# gd.net
KiCad netlist of a schematic drawn in Altium Designer
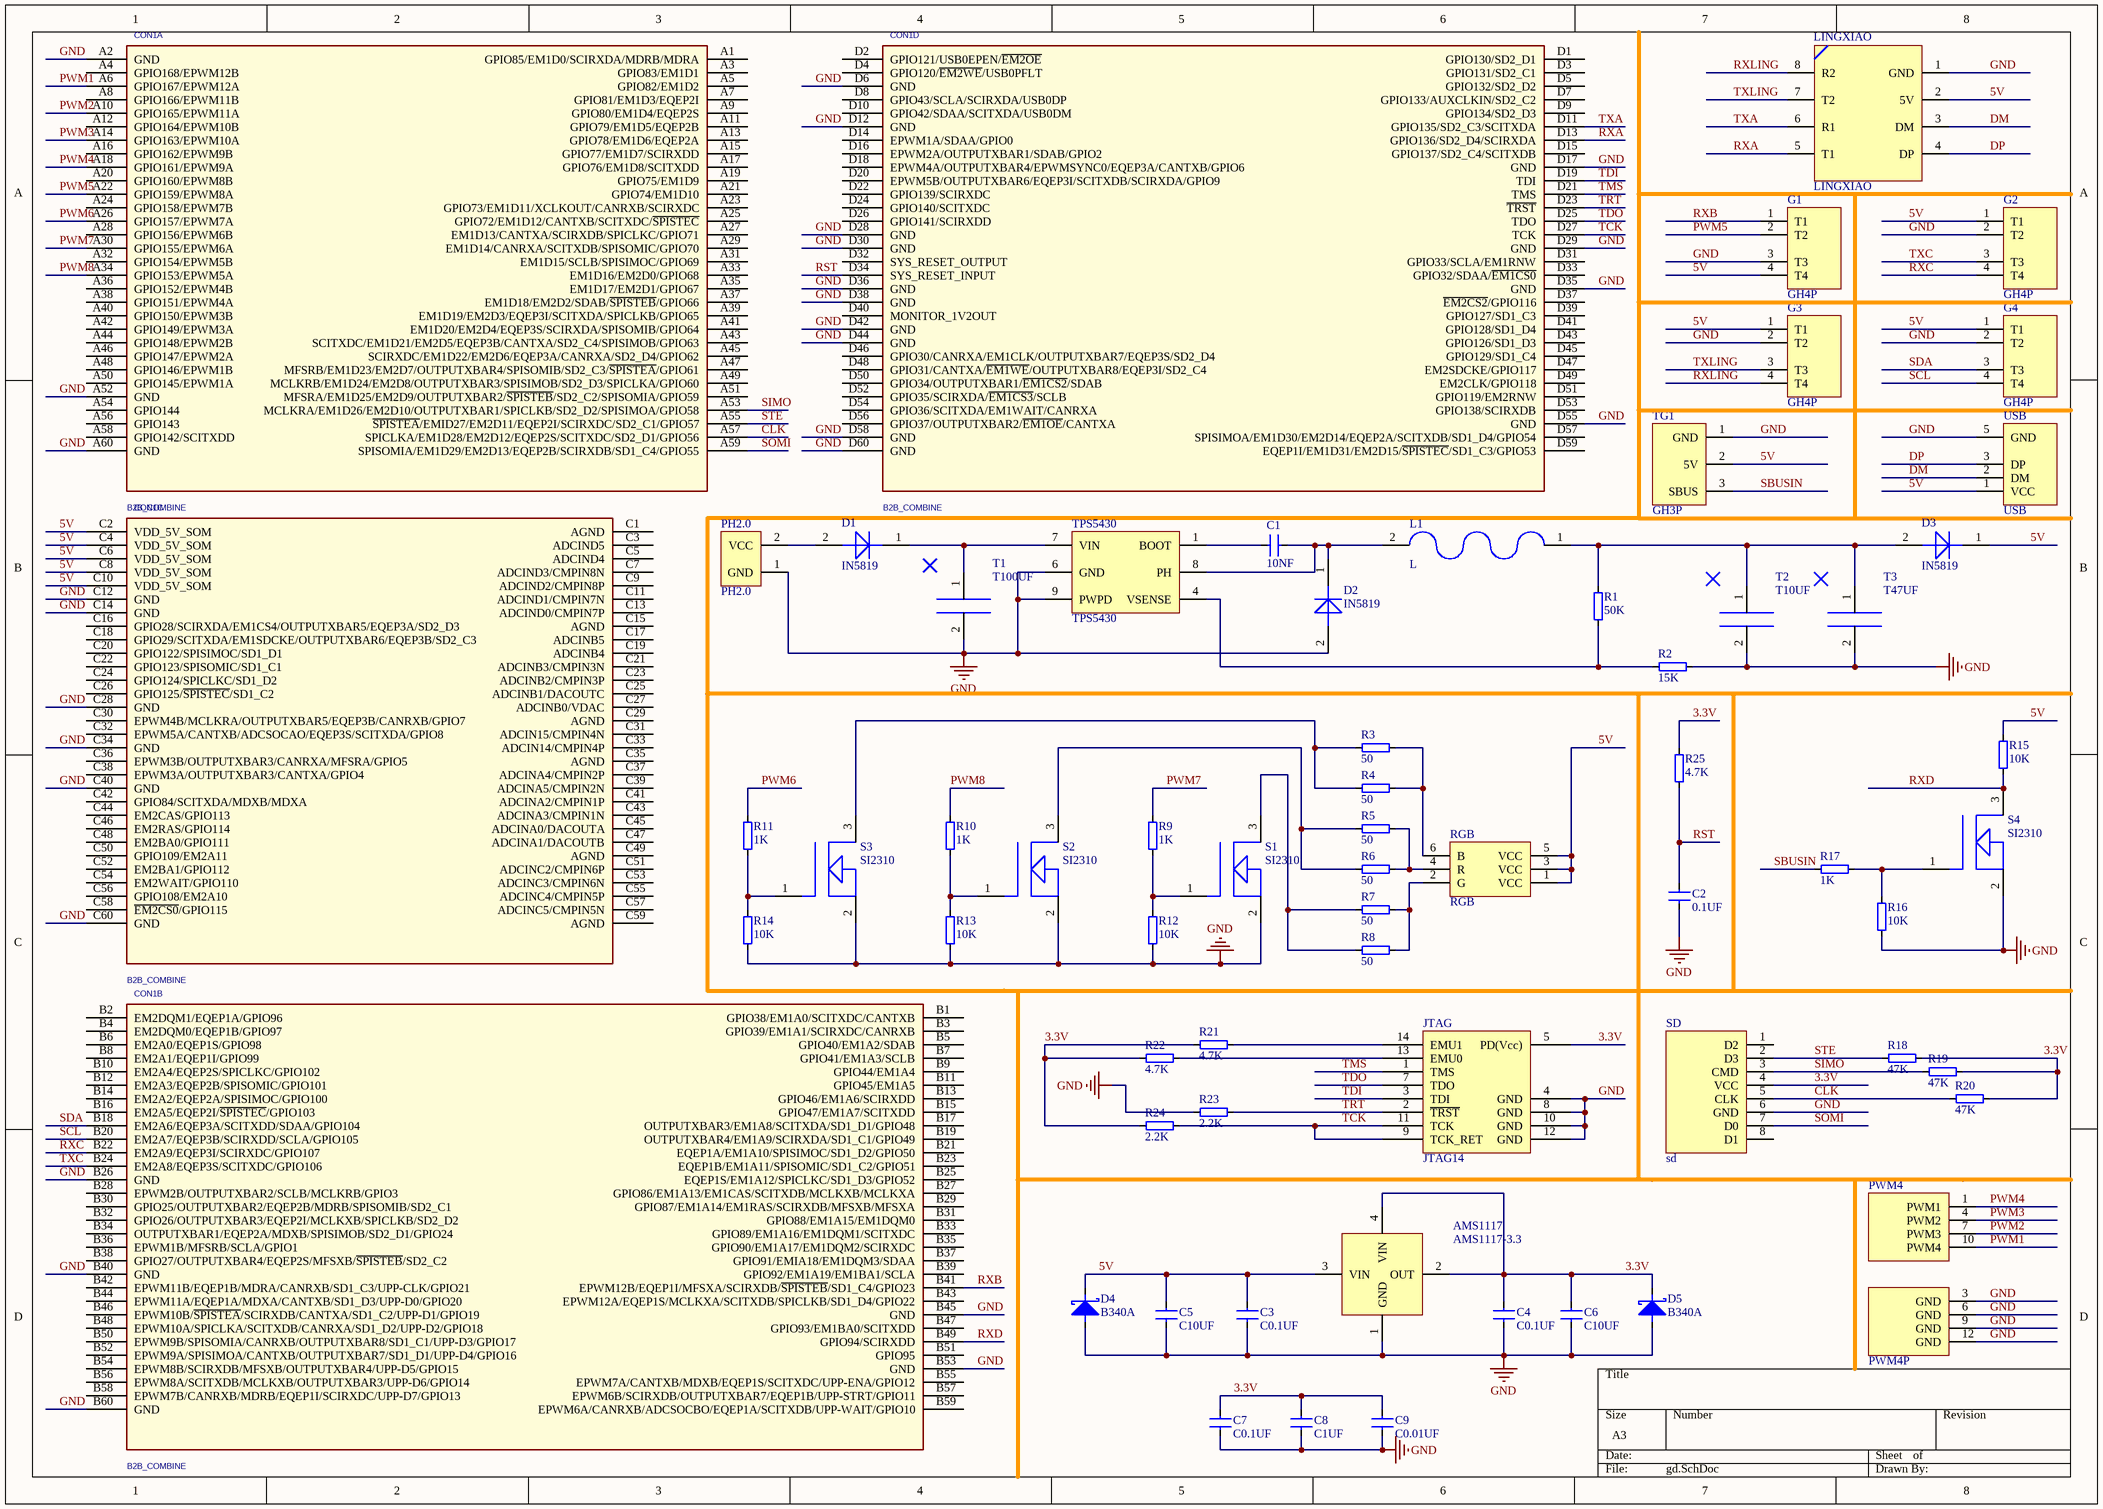
[diagram p0: gd.SchDoc]

(export (version "E")
  (design (tool "Eeschema 10.0.6"))
  (components
    (comp (ref "AMS1117")
      (value "AMS1117-3.3")
      (footprint "SOT-223")
      (libsource (lib "TD1") (part "AMS1117-3.3"))
    )
    (comp (ref "C1")
      (value "10NF")
      (footprint "C0603")
      (description "cap")
      (libsource (lib "小七的原理图库") (part "CAP"))
    )
    (comp (ref "C2")
      (value "0.1UF")
      (footprint "C0603")
      (description "cap")
      (libsource (lib "小七的原理图库") (part "CAP"))
    )
    (comp (ref "C3") (value "C0.1UF") (footprint "X0603") (libsource (lib "TD1") (part "C0.1UF")))
    (comp (ref "C4") (value "C0.1UF") (footprint "X0603") (libsource (lib "TD1") (part "C0.1UF")))
    (comp (ref "C5") (value "C10UF") (footprint "X0603") (libsource (lib "TD1") (part "C10UF")))
    (comp (ref "C6") (value "C10UF") (footprint "X0603") (libsource (lib "TD1") (part "C10UF")))
    (comp (ref "C7") (value "C0.1UF") (footprint "X0603") (libsource (lib "TD1") (part "C0.1UF")))
    (comp (ref "C8") (value "C1UF") (footprint "X0603") (libsource (lib "TD1") (part "C0.1UF")))
    (comp (ref "C9") (value "C0.01UF") (footprint "X0603") (libsource (lib "TD1") (part "C0.1UF")))
    (comp (ref "CON1")
      (value "B2B_COMBINE")
      (fields (field (name "MANUFACTURER") "连科"))
      (libsource (lib "B2B_SOM-TL2837x") (part "B2B_COMBINE_2"))
    )
    (comp (ref "D1") (value "IN5819") (footprint "IN5819") (libsource (lib "LINGXIAO") (part "IN5819")))
    (comp (ref "D2") (value "IN5819") (footprint "IN5819") (libsource (lib "LINGXIAO") (part "IN5819")))
    (comp (ref "D3") (value "IN5819") (footprint "IN5819") (libsource (lib "LINGXIAO") (part "IN5819")))
    (comp (ref "D4") (value "B340A") (footprint "B340A") (libsource (lib "TD1") (part "B340A")))
    (comp (ref "D5") (value "B340A") (footprint "B340A") (libsource (lib "TD1") (part "B340A")))
    (comp (ref "G1") (value "GH4P") (footprint "GH4P") (libsource (lib "LINGXIAO") (part "GH4P")))
    (comp (ref "G2") (value "GH4P") (footprint "GH4P") (libsource (lib "LINGXIAO") (part "GH4P")))
    (comp (ref "G3") (value "GH4P") (footprint "GH4P") (libsource (lib "LINGXIAO") (part "GH4P")))
    (comp (ref "G4") (value "GH4P") (footprint "GH4P") (libsource (lib "LINGXIAO") (part "GH4P")))
    (comp (ref "JTAG")
      (value "JTAG14")
      (footprint "CON2X7PA_2-54MM-N6")
      (libsource (lib "28377D_CORE") (part "JTAG-1"))
    )
    (comp (ref "L1") (value "L") (footprint "L") (libsource (lib "LINGXIAO") (part "L")))
    (comp (ref "LINGXIAO")
      (value "LINGXIAO")
      (footprint "LINGXIAO")
      (libsource (lib "LINGXIAO") (part "LINGXIAO"))
    )
    (comp (ref "PH2.0") (value "PH2.0") (footprint "PH2.0") (libsource (lib "LINGXIAO") (part "PH2.0")))
    (comp (ref "PWM4") (value "PWM4P") (footprint "PWM4P") (libsource (lib "LINGXIAO") (part "PWM4P")))
    (comp (ref "R1") (value "50K") (footprint "X0603") (libsource (lib "TD1") (part "R1K")))
    (comp (ref "R2") (value "15K") (footprint "X0603") (libsource (lib "TD1") (part "R1K")))
    (comp (ref "R3") (value "50") (footprint "X0603") (libsource (lib "TD1") (part "R1K")))
    (comp (ref "R4") (value "50") (footprint "X0603") (libsource (lib "TD1") (part "R1K")))
    (comp (ref "R5") (value "50") (footprint "X0603") (libsource (lib "TD1") (part "R1K")))
    (comp (ref "R6") (value "50") (footprint "X0603") (libsource (lib "TD1") (part "R1K")))
    (comp (ref "R7") (value "50") (footprint "X0603") (libsource (lib "TD1") (part "R1K")))
    (comp (ref "R8") (value "50") (footprint "X0603") (libsource (lib "TD1") (part "R1K")))
    (comp (ref "R9") (value "1K") (footprint "X0603") (libsource (lib "TD1") (part "R1K")))
    (comp (ref "R10") (value "1K") (footprint "X0603") (libsource (lib "TD1") (part "R1K")))
    (comp (ref "R11") (value "1K") (footprint "X0603") (libsource (lib "TD1") (part "R1K")))
    (comp (ref "R12") (value "10K") (footprint "X0603") (libsource (lib "TD1") (part "R1K")))
    (comp (ref "R13") (value "10K") (footprint "X0603") (libsource (lib "TD1") (part "R1K")))
    (comp (ref "R14") (value "10K") (footprint "X0603") (libsource (lib "TD1") (part "R1K")))
    (comp (ref "R15") (value "10K") (footprint "X0603") (libsource (lib "TD1") (part "R1K")))
    (comp (ref "R16") (value "10K") (footprint "X0603") (libsource (lib "TD1") (part "R1K")))
    (comp (ref "R17") (value "1K") (footprint "X0603") (libsource (lib "TD1") (part "R1K")))
    (comp (ref "R18") (value "47K") (footprint "X0603") (libsource (lib "TD1") (part "R1K")))
    (comp (ref "R19") (value "47K") (footprint "X0603") (libsource (lib "TD1") (part "R1K")))
    (comp (ref "R20") (value "47K") (footprint "X0603") (libsource (lib "TD1") (part "R1K")))
    (comp (ref "R21") (value "4.7K") (footprint "X0603") (libsource (lib "TD1") (part "R1K")))
    (comp (ref "R22") (value "4.7K") (footprint "X0603") (libsource (lib "TD1") (part "R1K")))
    (comp (ref "R23") (value "2.2K") (footprint "X0603") (libsource (lib "TD1") (part "R1K")))
    (comp (ref "R24") (value "2.2K") (footprint "X0603") (libsource (lib "TD1") (part "R1K")))
    (comp (ref "R25") (value "4.7K") (footprint "X0603") (libsource (lib "TD1") (part "R1K")))
    (comp (ref "RGB") (value "RGB") (footprint "RGB") (libsource (lib "LINGXIAO") (part "RGB")))
    (comp (ref "S1") (value "SI2310") (footprint "SI2310") (libsource (lib "LINGXIAO") (part "SI2310")))
    (comp (ref "S2") (value "SI2310") (footprint "SI2310") (libsource (lib "LINGXIAO") (part "SI2310")))
    (comp (ref "S3") (value "SI2310") (footprint "SI2310") (libsource (lib "LINGXIAO") (part "SI2310")))
    (comp (ref "S4") (value "SI2310") (footprint "SI2310") (libsource (lib "LINGXIAO") (part "SI2310")))
    (comp (ref "SD") (value "sd") (footprint "sd") (libsource (lib "SBD2") (part "sd")))
    (comp (ref "T1") (value "T100UF") (footprint "T100UF") (libsource (lib "LINGXIAO") (part "T100UF")))
    (comp (ref "T2") (value "T10UF") (footprint "T10UF") (libsource (lib "LINGXIAO") (part "T10UF")))
    (comp (ref "T3") (value "T47UF") (footprint "T47UF") (libsource (lib "LINGXIAO") (part "T47UF")))
    (comp (ref "TG1") (value "GH3P") (footprint "GH3P") (libsource (lib "LINGXIAO") (part "GH3P")))
    (comp (ref "TPS5430")
      (value "TPS5430")
      (footprint "TPS5430")
      (libsource (lib "LINGXIAO") (part "TPS5430"))
    )
    (comp (ref "USB") (value "USB") (footprint "USB") (libsource (lib "LINGXIAO") (part "USB")))
  )
  (nets
    (net (code "1") (name "/3.3V") (class "Default")
      (node (ref "AMS1117") (pin "2") (pinfunction "OUT_2") (pintype "passive"))
      (node (ref "AMS1117") (pin "4") (pinfunction "VIN_4") (pintype "passive"))
      (node (ref "C4") (pin "2") (pinfunction "2_2") (pintype "passive"))
      (node (ref "C6") (pin "2") (pinfunction "2_2") (pintype "passive"))
      (node (ref "C7") (pin "2") (pinfunction "2_2") (pintype "passive"))
      (node (ref "C8") (pin "2") (pinfunction "2_2") (pintype "passive"))
      (node (ref "C9") (pin "2") (pinfunction "2_2") (pintype "passive"))
      (node (ref "D5") (pin "K") (pinfunction "2_K") (pintype "passive"))
      (node (ref "JTAG") (pin "5") (pinfunction "PD(Vcc)_5") (pintype "passive"))
      (node (ref "R18") (pin "2") (pinfunction "2_2") (pintype "passive"))
      (node (ref "R19") (pin "2") (pinfunction "2_2") (pintype "passive"))
      (node (ref "R20") (pin "2") (pinfunction "2_2") (pintype "passive"))
      (node (ref "R21") (pin "1") (pinfunction "1_1") (pintype "passive"))
      (node (ref "R22") (pin "1") (pinfunction "1_1") (pintype "passive"))
      (node (ref "R24") (pin "1") (pinfunction "1_1") (pintype "passive"))
      (node (ref "R25") (pin "2") (pinfunction "2_2") (pintype "passive"))
      (node (ref "SD") (pin "4") (pinfunction "VCC_4") (pintype "passive"))
    )
    (net (code "2") (name "/5V") (class "Default")
      (node (ref "AMS1117") (pin "3") (pinfunction "VIN_3") (pintype "passive"))
      (node (ref "C3") (pin "2") (pinfunction "2_2") (pintype "passive"))
      (node (ref "C5") (pin "2") (pinfunction "2_2") (pintype "passive"))
      (node (ref "CON1") (pin "C10") (pinfunction "VDD_5V_SOM_C10") (pintype "power_in"))
      (node (ref "CON1") (pin "C2") (pinfunction "VDD_5V_SOM_C2") (pintype "power_in"))
      (node (ref "CON1") (pin "C4") (pinfunction "VDD_5V_SOM_C4") (pintype "power_in"))
      (node (ref "CON1") (pin "C6") (pinfunction "VDD_5V_SOM_C6") (pintype "power_in"))
      (node (ref "CON1") (pin "C8") (pinfunction "VDD_5V_SOM_C8") (pintype "power_in"))
      (node (ref "D3") (pin "1") (pinfunction "T1_1") (pintype "passive"))
      (node (ref "D4") (pin "K") (pinfunction "2_K") (pintype "passive"))
      (node (ref "G1") (pin "4") (pinfunction "T4_4") (pintype "passive"))
      (node (ref "G2") (pin "1") (pinfunction "T1_1") (pintype "passive"))
      (node (ref "G3") (pin "1") (pinfunction "T1_1") (pintype "passive"))
      (node (ref "G4") (pin "1") (pinfunction "T1_1") (pintype "passive"))
      (node (ref "LINGXIAO") (pin "2") (pinfunction "5V_2") (pintype "passive"))
      (node (ref "R15") (pin "2") (pinfunction "2_2") (pintype "passive"))
      (node (ref "RGB") (pin "1") (pinfunction "VCC_1") (pintype "passive"))
      (node (ref "RGB") (pin "3") (pinfunction "VCC_3") (pintype "passive"))
      (node (ref "RGB") (pin "5") (pinfunction "VCC_5") (pintype "passive"))
      (node (ref "TG1") (pin "2") (pinfunction "5V_2") (pintype "passive"))
      (node (ref "USB") (pin "1") (pinfunction "VCC_1") (pintype "passive"))
    )
    (net (code "3") (name "/CLK") (class "Default")
      (node (ref "CON1") (pin "A57") (pinfunction "SPICLKA/EM1D28/EM2D12/EQEP2S/SCITXDC/SD2_D1/GPIO56_A57") (pintype "passive"))
      (node (ref "R20") (pin "1") (pinfunction "1_1") (pintype "passive"))
      (node (ref "SD") (pin "5") (pinfunction "CLK_5") (pintype "passive"))
    )
    (net (code "4") (name "/DM") (class "Default")
      (node (ref "LINGXIAO") (pin "3") (pinfunction "DM_3") (pintype "passive"))
      (node (ref "USB") (pin "2") (pinfunction "DM_2") (pintype "passive"))
    )
    (net (code "5") (name "/DP") (class "Default")
      (node (ref "LINGXIAO") (pin "4") (pinfunction "DP_4") (pintype "passive"))
      (node (ref "USB") (pin "3") (pinfunction "DP_3") (pintype "passive"))
    )
    (net (code "6") (name "/PWM1") (class "Default")
      (node (ref "CON1") (pin "A6") (pinfunction "GPIO167/EPWM12A_A6") (pintype "passive"))
      (node (ref "PWM4") (pin "10") (pinfunction "PWM4_10") (pintype "passive"))
    )
    (net (code "7") (name "/PWM2") (class "Default")
      (node (ref "CON1") (pin "A10") (pinfunction "GPIO165/EPWM11A_A10") (pintype "passive"))
      (node (ref "PWM4") (pin "7") (pinfunction "PWM3_7") (pintype "passive"))
    )
    (net (code "8") (name "/PWM3") (class "Default")
      (node (ref "CON1") (pin "A14") (pinfunction "GPIO163/EPWM10A_A14") (pintype "passive"))
      (node (ref "PWM4") (pin "4") (pinfunction "PWM2_4") (pintype "passive"))
    )
    (net (code "9") (name "/PWM4") (class "Default")
      (node (ref "CON1") (pin "A18") (pinfunction "GPIO161/EPWM9A_A18") (pintype "passive"))
      (node (ref "PWM4") (pin "1") (pinfunction "PWM1_1") (pintype "passive"))
    )
    (net (code "10") (name "/PWM5") (class "Default")
      (node (ref "CON1") (pin "A22") (pinfunction "GPIO159/EPWM8A_A22") (pintype "passive"))
      (node (ref "G1") (pin "2") (pinfunction "T2_2") (pintype "passive"))
    )
    (net (code "11") (name "/PWM6") (class "Default")
      (node (ref "CON1") (pin "A26") (pinfunction "GPIO157/EPWM7A_A26") (pintype "passive"))
      (node (ref "R11") (pin "2") (pinfunction "2_2") (pintype "passive"))
    )
    (net (code "12") (name "/PWM7") (class "Default")
      (node (ref "CON1") (pin "A30") (pinfunction "GPIO155/EPWM6A_A30") (pintype "passive"))
      (node (ref "R9") (pin "2") (pinfunction "2_2") (pintype "passive"))
    )
    (net (code "13") (name "/PWM8") (class "Default")
      (node (ref "CON1") (pin "A34") (pinfunction "GPIO153/EPWM5A_A34") (pintype "passive"))
      (node (ref "R10") (pin "2") (pinfunction "2_2") (pintype "passive"))
    )
    (net (code "14") (name "/RST") (class "Default")
      (node (ref "C2") (pin "2") (pinfunction "2_2") (pintype "passive"))
      (node (ref "CON1") (pin "D34") (pinfunction "SYS_RESET_INPUT_D34") (pintype "passive"))
      (node (ref "R25") (pin "1") (pinfunction "1_1") (pintype "passive"))
    )
    (net (code "15") (name "/RXA") (class "Default")
      (node (ref "CON1") (pin "D13") (pinfunction "GPIO136/SD2_D4/SCIRXDA_D13") (pintype "passive"))
      (node (ref "LINGXIAO") (pin "5") (pinfunction "T1_5") (pintype "passive"))
    )
    (net (code "16") (name "/RXB") (class "Default")
      (node (ref "CON1") (pin "B41") (pinfunction "EPWM12B/EQEP1I/MFSXA/SCIRXDB/~{SPISTEB}/SD1_C4/GPIO23_B41") (pintype "passive"))
      (node (ref "G1") (pin "1") (pinfunction "T1_1") (pintype "passive"))
    )
    (net (code "17") (name "/RXC") (class "Default")
      (node (ref "CON1") (pin "B22") (pinfunction "EM2A9/EQEP3I/SCIRXDC/GPIO107_B22") (pintype "passive"))
      (node (ref "G2") (pin "4") (pinfunction "T4_4") (pintype "passive"))
    )
    (net (code "18") (name "/RXD") (class "Default")
      (node (ref "CON1") (pin "B49") (pinfunction "GPIO94/SCIRXDD_B49") (pintype "passive"))
      (node (ref "R15") (pin "1") (pinfunction "1_1") (pintype "passive"))
      (node (ref "S4") (pin "3") (pinfunction "B_3") (pintype "passive"))
    )
    (net (code "19") (name "/RXLING") (class "Default")
      (node (ref "G3") (pin "4") (pinfunction "T4_4") (pintype "passive"))
      (node (ref "LINGXIAO") (pin "8") (pinfunction "R2_8") (pintype "passive"))
    )
    (net (code "20") (name "/SBUSIN") (class "Default")
      (node (ref "R17") (pin "1") (pinfunction "1_1") (pintype "passive"))
      (node (ref "TG1") (pin "3") (pinfunction "SBUS_3") (pintype "passive"))
    )
    (net (code "21") (name "/SCL") (class "Default")
      (node (ref "CON1") (pin "B20") (pinfunction "EM2A7/EQEP3B/SCIRXDD/SCLA/GPIO105_B20") (pintype "passive"))
      (node (ref "G4") (pin "4") (pinfunction "T4_4") (pintype "passive"))
    )
    (net (code "22") (name "/SDA") (class "Default")
      (node (ref "CON1") (pin "B18") (pinfunction "EM2A6/EQEP3A/SCITXDD/SDAA/GPIO104_B18") (pintype "passive"))
      (node (ref "G4") (pin "3") (pinfunction "T3_3") (pintype "passive"))
    )
    (net (code "23") (name "/SIMO") (class "Default")
      (node (ref "CON1") (pin "A53") (pinfunction "MCLKRA/EM1D26/EM2D10/OUTPUTXBAR1/SPICLKB/SD2_D2/SPISIMOA/GPIO58_A53") (pintype "passive"))
      (node (ref "R19") (pin "1") (pinfunction "1_1") (pintype "passive"))
      (node (ref "SD") (pin "3") (pinfunction "CMD_3") (pintype "passive"))
    )
    (net (code "24") (name "/SOMI") (class "Default")
      (node (ref "CON1") (pin "A59") (pinfunction "SPISOMIA/EM1D29/EM2D13/EQEP2B/SCIRXDB/SD1_C4/GPIO55_A59") (pintype "passive"))
      (node (ref "SD") (pin "7") (pinfunction "D0_7") (pintype "passive"))
    )
    (net (code "25") (name "/STE") (class "Default")
      (node (ref "CON1") (pin "A55") (pinfunction "~{SPISTEA}/EMID27/EM2D11/EQEP2I/SCIRXDC/SD2_C1/GPIO57_A55") (pintype "passive"))
      (node (ref "R18") (pin "1") (pinfunction "1_1") (pintype "passive"))
      (node (ref "SD") (pin "2") (pinfunction "D3_2") (pintype "passive"))
    )
    (net (code "26") (name "/TCK") (class "Default")
      (node (ref "CON1") (pin "D27") (pinfunction "TCK_D27") (pintype "passive"))
      (node (ref "JTAG") (pin "11") (pinfunction "TCK_11") (pintype "passive"))
      (node (ref "JTAG") (pin "9") (pinfunction "TCK_RET_9") (pintype "passive"))
      (node (ref "R24") (pin "2") (pinfunction "2_2") (pintype "passive"))
    )
    (net (code "27") (name "/TDI") (class "Default")
      (node (ref "CON1") (pin "D19") (pinfunction "TDI_D19") (pintype "passive"))
      (node (ref "JTAG") (pin "3") (pinfunction "TDI_3") (pintype "passive"))
    )
    (net (code "28") (name "/TDO") (class "Default")
      (node (ref "CON1") (pin "D25") (pinfunction "TDO_D25") (pintype "passive"))
      (node (ref "JTAG") (pin "7") (pinfunction "TDO_7") (pintype "passive"))
    )
    (net (code "29") (name "/TMS") (class "Default")
      (node (ref "CON1") (pin "D21") (pinfunction "TMS_D21") (pintype "passive"))
      (node (ref "JTAG") (pin "1") (pinfunction "TMS_1") (pintype "passive"))
    )
    (net (code "30") (name "/TRT") (class "Default")
      (node (ref "CON1") (pin "D23") (pinfunction "~{TRST}_D23") (pintype "passive"))
      (node (ref "JTAG") (pin "2") (pinfunction "~{TRST}_2") (pintype "passive"))
      (node (ref "R23") (pin "2") (pinfunction "2_2") (pintype "passive"))
    )
    (net (code "31") (name "/TXA") (class "Default")
      (node (ref "CON1") (pin "D11") (pinfunction "GPIO135/SD2_C3/SCITXDA_D11") (pintype "passive"))
      (node (ref "LINGXIAO") (pin "6") (pinfunction "R1_6") (pintype "passive"))
    )
    (net (code "32") (name "/TXC") (class "Default")
      (node (ref "CON1") (pin "B24") (pinfunction "EM2A8/EQEP3S/SCITXDC/GPIO106_B24") (pintype "passive"))
      (node (ref "G2") (pin "3") (pinfunction "T3_3") (pintype "passive"))
    )
    (net (code "33") (name "/TXLING") (class "Default")
      (node (ref "G3") (pin "3") (pinfunction "T3_3") (pintype "passive"))
      (node (ref "LINGXIAO") (pin "7") (pinfunction "T2_7") (pintype "passive"))
    )
    (net (code "34") (name "GND") (class "Default")
      (node (ref "AMS1117") (pin "1") (pinfunction "GND_1") (pintype "passive"))
      (node (ref "C2") (pin "1") (pinfunction "1_1") (pintype "passive"))
      (node (ref "C3") (pin "1") (pinfunction "1_1") (pintype "passive"))
      (node (ref "C4") (pin "1") (pinfunction "1_1") (pintype "passive"))
      (node (ref "C5") (pin "1") (pinfunction "1_1") (pintype "passive"))
      (node (ref "C6") (pin "1") (pinfunction "1_1") (pintype "passive"))
      (node (ref "C7") (pin "1") (pinfunction "1_1") (pintype "passive"))
      (node (ref "C8") (pin "1") (pinfunction "1_1") (pintype "passive"))
      (node (ref "C9") (pin "1") (pinfunction "1_1") (pintype "passive"))
      (node (ref "CON1") (pin "A2") (pinfunction "GND_A2") (pintype "power_in"))
      (node (ref "CON1") (pin "A52") (pinfunction "GND_A52") (pintype "power_in"))
      (node (ref "CON1") (pin "A60") (pinfunction "GND_A60") (pintype "power_in"))
      (node (ref "CON1") (pin "B26") (pinfunction "GND_B26") (pintype "power_in"))
      (node (ref "CON1") (pin "B40") (pinfunction "GND_B40") (pintype "power_in"))
      (node (ref "CON1") (pin "B45") (pinfunction "GND_B45") (pintype "power_in"))
      (node (ref "CON1") (pin "B53") (pinfunction "GND_B53") (pintype "power_in"))
      (node (ref "CON1") (pin "B60") (pinfunction "GND_B60") (pintype "power_in"))
      (node (ref "CON1") (pin "C12") (pinfunction "GND_C12") (pintype "power_in"))
      (node (ref "CON1") (pin "C14") (pinfunction "GND_C14") (pintype "power_in"))
      (node (ref "CON1") (pin "C28") (pinfunction "GND_C28") (pintype "power_in"))
      (node (ref "CON1") (pin "C34") (pinfunction "GND_C34") (pintype "power_in"))
      (node (ref "CON1") (pin "C40") (pinfunction "GND_C40") (pintype "power_in"))
      (node (ref "CON1") (pin "C60") (pinfunction "GND_C60") (pintype "power_in"))
      (node (ref "CON1") (pin "D12") (pinfunction "GND_D12") (pintype "power_in"))
      (node (ref "CON1") (pin "D17") (pinfunction "GND_D17") (pintype "power_in"))
      (node (ref "CON1") (pin "D28") (pinfunction "GND_D28") (pintype "power_in"))
      (node (ref "CON1") (pin "D29") (pinfunction "GND_D29") (pintype "power_in"))
      (node (ref "CON1") (pin "D30") (pinfunction "GND_D30") (pintype "power_in"))
      (node (ref "CON1") (pin "D35") (pinfunction "GND_D35") (pintype "power_in"))
      (node (ref "CON1") (pin "D36") (pinfunction "GND_D36") (pintype "power_in"))
      (node (ref "CON1") (pin "D38") (pinfunction "GND_D38") (pintype "power_in"))
      (node (ref "CON1") (pin "D42") (pinfunction "GND_D42") (pintype "power_in"))
      (node (ref "CON1") (pin "D44") (pinfunction "GND_D44") (pintype "power_in"))
      (node (ref "CON1") (pin "D55") (pinfunction "GND_D55") (pintype "power_in"))
      (node (ref "CON1") (pin "D58") (pinfunction "GND_D58") (pintype "power_in"))
      (node (ref "CON1") (pin "D6") (pinfunction "GND_D6") (pintype "power_in"))
      (node (ref "CON1") (pin "D60") (pinfunction "GND_D60") (pintype "power_in"))
      (node (ref "D2") (pin "2") (pinfunction "T2_2") (pintype "passive"))
      (node (ref "D4") (pin "A") (pinfunction "1_A") (pintype "passive"))
      (node (ref "D5") (pin "A") (pinfunction "1_A") (pintype "passive"))
      (node (ref "G1") (pin "3") (pinfunction "T3_3") (pintype "passive"))
      (node (ref "G2") (pin "2") (pinfunction "T2_2") (pintype "passive"))
      (node (ref "G3") (pin "2") (pinfunction "T2_2") (pintype "passive"))
      (node (ref "G4") (pin "2") (pinfunction "T2_2") (pintype "passive"))
      (node (ref "JTAG") (pin "10") (pinfunction "GND_10") (pintype "passive"))
      (node (ref "JTAG") (pin "12") (pinfunction "GND_12") (pintype "passive"))
      (node (ref "JTAG") (pin "4") (pinfunction "GND_4") (pintype "passive"))
      (node (ref "JTAG") (pin "8") (pinfunction "GND_8") (pintype "passive"))
      (node (ref "LINGXIAO") (pin "1") (pinfunction "GND_1") (pintype "passive"))
      (node (ref "PH2.0") (pin "1") (pinfunction "GND_1") (pintype "passive"))
      (node (ref "PWM4") (pin "12") (pinfunction "GND_12") (pintype "passive"))
      (node (ref "PWM4") (pin "3") (pinfunction "GND_3") (pintype "passive"))
      (node (ref "PWM4") (pin "6") (pinfunction "GND_6") (pintype "passive"))
      (node (ref "PWM4") (pin "9") (pinfunction "GND_9") (pintype "passive"))
      (node (ref "R12") (pin "1") (pinfunction "1_1") (pintype "passive"))
      (node (ref "R13") (pin "1") (pinfunction "1_1") (pintype "passive"))
      (node (ref "R14") (pin "1") (pinfunction "1_1") (pintype "passive"))
      (node (ref "R16") (pin "2") (pinfunction "2_2") (pintype "passive"))
      (node (ref "R2") (pin "2") (pinfunction "2_2") (pintype "passive"))
      (node (ref "R23") (pin "1") (pinfunction "1_1") (pintype "passive"))
      (node (ref "S1") (pin "2") (pinfunction "B_2") (pintype "passive"))
      (node (ref "S2") (pin "2") (pinfunction "B_2") (pintype "passive"))
      (node (ref "S3") (pin "2") (pinfunction "B_2") (pintype "passive"))
      (node (ref "S4") (pin "2") (pinfunction "B_2") (pintype "passive"))
      (node (ref "SD") (pin "6") (pinfunction "GND_6") (pintype "passive"))
      (node (ref "T1") (pin "2") (pinfunction "B_2") (pintype "passive"))
      (node (ref "T2") (pin "2") (pinfunction "B_2") (pintype "passive"))
      (node (ref "T3") (pin "2") (pinfunction "B_2") (pintype "passive"))
      (node (ref "TG1") (pin "1") (pinfunction "GND_1") (pintype "passive"))
      (node (ref "TPS5430") (pin "6") (pinfunction "GND_6") (pintype "passive"))
      (node (ref "TPS5430") (pin "9") (pinfunction "PWPD_9") (pintype "passive"))
      (node (ref "USB") (pin "5") (pinfunction "GND_5") (pintype "passive"))
    )
    (net (code "35") (name "Net-(D1-T1)") (class "Default")
      (node (ref "D1") (pin "1") (pinfunction "T1_1") (pintype "passive"))
      (node (ref "T1") (pin "1") (pinfunction "B_1") (pintype "passive"))
      (node (ref "TPS5430") (pin "7") (pinfunction "VIN_7") (pintype "passive"))
    )
    (net (code "36") (name "Net-(D1-T2)") (class "Default")
      (node (ref "D1") (pin "2") (pinfunction "T2_2") (pintype "passive"))
      (node (ref "PH2.0") (pin "2") (pinfunction "VCC_2") (pintype "passive"))
    )
    (net (code "37") (name "Net-(D2-T1)") (class "Default")
      (node (ref "C1") (pin "2") (pinfunction "2_2") (pintype "passive"))
      (node (ref "D2") (pin "1") (pinfunction "T1_1") (pintype "passive"))
      (node (ref "L1") (pin "2") (pinfunction "T4_2") (pintype "passive"))
      (node (ref "TPS5430") (pin "8") (pinfunction "PH_8") (pintype "passive"))
    )
    (net (code "38") (name "Net-(D3-T2)") (class "Default")
      (node (ref "D3") (pin "2") (pinfunction "T2_2") (pintype "passive"))
      (node (ref "L1") (pin "1") (pinfunction "T3_1") (pintype "passive"))
      (node (ref "R1") (pin "2") (pinfunction "2_2") (pintype "passive"))
      (node (ref "T2") (pin "1") (pinfunction "B_1") (pintype "passive"))
      (node (ref "T3") (pin "1") (pinfunction "B_1") (pintype "passive"))
    )
    (net (code "39") (name "Net-(JTAG-EMU0)") (class "Default")
      (node (ref "JTAG") (pin "13") (pinfunction "EMU0_13") (pintype "passive"))
      (node (ref "R22") (pin "2") (pinfunction "2_2") (pintype "passive"))
    )
    (net (code "40") (name "Net-(JTAG-EMU1)") (class "Default")
      (node (ref "JTAG") (pin "14") (pinfunction "EMU1_14") (pintype "passive"))
      (node (ref "R21") (pin "2") (pinfunction "2_2") (pintype "passive"))
    )
    (net (code "41") (name "Net-(R3-Pad1)") (class "Default")
      (node (ref "R3") (pin "1") (pinfunction "1_1") (pintype "passive"))
      (node (ref "R4") (pin "1") (pinfunction "1_1") (pintype "passive"))
      (node (ref "S3") (pin "3") (pinfunction "B_3") (pintype "passive"))
    )
    (net (code "42") (name "Net-(R5-Pad1)") (class "Default")
      (node (ref "R5") (pin "1") (pinfunction "1_1") (pintype "passive"))
      (node (ref "R6") (pin "1") (pinfunction "1_1") (pintype "passive"))
      (node (ref "S2") (pin "3") (pinfunction "B_3") (pintype "passive"))
    )
    (net (code "43") (name "Net-(R7-Pad1)") (class "Default")
      (node (ref "R7") (pin "1") (pinfunction "1_1") (pintype "passive"))
      (node (ref "R8") (pin "1") (pinfunction "1_1") (pintype "passive"))
      (node (ref "S1") (pin "3") (pinfunction "B_3") (pintype "passive"))
    )
    (net (code "44") (name "Net-(R10-Pad1)") (class "Default")
      (node (ref "R10") (pin "1") (pinfunction "1_1") (pintype "passive"))
      (node (ref "R13") (pin "2") (pinfunction "2_2") (pintype "passive"))
      (node (ref "S2") (pin "1") (pinfunction "B_1") (pintype "passive"))
    )
    (net (code "45") (name "Net-(R11-Pad1)") (class "Default")
      (node (ref "R11") (pin "1") (pinfunction "1_1") (pintype "passive"))
      (node (ref "R14") (pin "2") (pinfunction "2_2") (pintype "passive"))
      (node (ref "S3") (pin "1") (pinfunction "B_1") (pintype "passive"))
    )
    (net (code "46") (name "Net-(R12-Pad2)") (class "Default")
      (node (ref "R12") (pin "2") (pinfunction "2_2") (pintype "passive"))
      (node (ref "R9") (pin "1") (pinfunction "1_1") (pintype "passive"))
      (node (ref "S1") (pin "1") (pinfunction "B_1") (pintype "passive"))
    )
    (net (code "47") (name "Net-(R16-Pad1)") (class "Default")
      (node (ref "R16") (pin "1") (pinfunction "1_1") (pintype "passive"))
      (node (ref "R17") (pin "2") (pinfunction "2_2") (pintype "passive"))
      (node (ref "S4") (pin "1") (pinfunction "B_1") (pintype "passive"))
    )
    (net (code "48") (name "Net-(RGB-B)") (class "Default")
      (node (ref "R3") (pin "2") (pinfunction "2_2") (pintype "passive"))
      (node (ref "R4") (pin "2") (pinfunction "2_2") (pintype "passive"))
      (node (ref "RGB") (pin "6") (pinfunction "B_6") (pintype "passive"))
    )
    (net (code "49") (name "Net-(RGB-G)") (class "Default")
      (node (ref "R7") (pin "2") (pinfunction "2_2") (pintype "passive"))
      (node (ref "R8") (pin "2") (pinfunction "2_2") (pintype "passive"))
      (node (ref "RGB") (pin "2") (pinfunction "G_2") (pintype "passive"))
    )
    (net (code "50") (name "Net-(RGB-R)") (class "Default")
      (node (ref "R5") (pin "2") (pinfunction "2_2") (pintype "passive"))
      (node (ref "R6") (pin "2") (pinfunction "2_2") (pintype "passive"))
      (node (ref "RGB") (pin "4") (pinfunction "R_4") (pintype "passive"))
    )
    (net (code "51") (name "Net-(TPS5430-BOOT)") (class "Default")
      (node (ref "C1") (pin "1") (pinfunction "1_1") (pintype "passive"))
      (node (ref "TPS5430") (pin "1") (pinfunction "BOOT_1") (pintype "passive"))
    )
    (net (code "52") (name "Net-(TPS5430-VSENSE)") (class "Default")
      (node (ref "R1") (pin "1") (pinfunction "1_1") (pintype "passive"))
      (node (ref "R2") (pin "1") (pinfunction "1_1") (pintype "passive"))
      (node (ref "TPS5430") (pin "4") (pinfunction "VSENSE_4") (pintype "passive"))
    )
    (net (code "53") (name "unconnected-(CON1A-EM1D13{slash}CANTXA{slash}SCIRXDB{slash}SPICLKC{slash}GPIO71-PadA27)") (class "Default")
      (node (ref "CON1") (pin "A27") (pinfunction "EM1D13/CANTXA/SCIRXDB/SPICLKC/GPIO71_A27") (pintype "passive"))
    )
    (net (code "54") (name "unconnected-(CON1A-EM1D14{slash}CANRXA{slash}SCITXDB{slash}SPISOMIC{slash}GPIO70-PadA29)") (class "Default")
      (node (ref "CON1") (pin "A29") (pinfunction "EM1D14/CANRXA/SCITXDB/SPISOMIC/GPIO70_A29") (pintype "passive"))
    )
    (net (code "55") (name "unconnected-(CON1A-EM1D15{slash}SCLB{slash}SPISIMOC{slash}GPIO69-PadA31)") (class "Default")
      (node (ref "CON1") (pin "A31") (pinfunction "EM1D15/SCLB/SPISIMOC/GPIO69_A31") (pintype "passive"))
    )
    (net (code "56") (name "unconnected-(CON1A-EM1D16{slash}EM2D0{slash}GPIO68-PadA33)") (class "Default")
      (node (ref "CON1") (pin "A33") (pinfunction "EM1D16/EM2D0/GPIO68_A33") (pintype "passive"))
    )
    (net (code "57") (name "unconnected-(CON1A-EM1D17{slash}EM2D1{slash}GPIO67-PadA35)") (class "Default")
      (node (ref "CON1") (pin "A35") (pinfunction "EM1D17/EM2D1/GPIO67_A35") (pintype "passive"))
    )
    (net (code "58") (name "unconnected-(CON1A-EM1D18{slash}EM2D2{slash}SDAB{slash}~{SPISTEB}{slash}GPIO66-PadA37)") (class "Default")
      (node (ref "CON1") (pin "A37") (pinfunction "EM1D18/EM2D2/SDAB/~{SPISTEB}/GPIO66_A37") (pintype "passive"))
    )
    (net (code "59") (name "unconnected-(CON1A-EM1D19{slash}EM2D3{slash}EQEP3I{slash}SCITXDA{slash}SPICLKB{slash}GPIO65-PadA39)") (class "Default")
      (node (ref "CON1") (pin "A39") (pinfunction "EM1D19/EM2D3/EQEP3I/SCITXDA/SPICLKB/GPIO65_A39") (pintype "passive"))
    )
    (net (code "60") (name "unconnected-(CON1A-EM1D20{slash}EM2D4{slash}EQEP3S{slash}SCIRXDA{slash}SPISOMIB{slash}GPIO64-PadA41)") (class "Default")
      (node (ref "CON1") (pin "A41") (pinfunction "EM1D20/EM2D4/EQEP3S/SCIRXDA/SPISOMIB/GPIO64_A41") (pintype "passive"))
    )
    (net (code "61") (name "unconnected-(CON1A-GPIO72{slash}EM1D12{slash}CANTXB{slash}SCITXDC{slash}~{SPISTEC}-PadA25)") (class "Default")
      (node (ref "CON1") (pin "A25") (pinfunction "GPIO72/EM1D12/CANTXB/SCITXDC/~{SPISTEC}_A25") (pintype "passive"))
    )
    (net (code "62") (name "unconnected-(CON1A-GPIO73{slash}EM1D11{slash}XCLKOUT{slash}CANRXB{slash}SCIRXDC-PadA23)") (class "Default")
      (node (ref "CON1") (pin "A23") (pinfunction "GPIO73/EM1D11/XCLKOUT/CANRXB/SCIRXDC_A23") (pintype "passive"))
    )
    (net (code "63") (name "unconnected-(CON1A-GPIO74{slash}EM1D10-PadA21)") (class "Default")
      (node (ref "CON1") (pin "A21") (pinfunction "GPIO74/EM1D10_A21") (pintype "passive"))
    )
    (net (code "64") (name "unconnected-(CON1A-GPIO75{slash}EM1D9-PadA19)") (class "Default")
      (node (ref "CON1") (pin "A19") (pinfunction "GPIO75/EM1D9_A19") (pintype "passive"))
    )
    (net (code "65") (name "unconnected-(CON1A-GPIO76{slash}EM1D8{slash}SCITXDD-PadA17)") (class "Default")
      (node (ref "CON1") (pin "A17") (pinfunction "GPIO76/EM1D8/SCITXDD_A17") (pintype "passive"))
    )
    (net (code "66") (name "unconnected-(CON1A-GPIO77{slash}EM1D7{slash}SCIRXDD-PadA15)") (class "Default")
      (node (ref "CON1") (pin "A15") (pinfunction "GPIO77/EM1D7/SCIRXDD_A15") (pintype "passive"))
    )
    (net (code "67") (name "unconnected-(CON1A-GPIO78{slash}EM1D6{slash}EQEP2A-PadA13)") (class "Default")
      (node (ref "CON1") (pin "A13") (pinfunction "GPIO78/EM1D6/EQEP2A_A13") (pintype "passive"))
    )
    (net (code "68") (name "unconnected-(CON1A-GPIO79{slash}EM1D5{slash}EQEP2B-PadA11)") (class "Default")
      (node (ref "CON1") (pin "A11") (pinfunction "GPIO79/EM1D5/EQEP2B_A11") (pintype "passive"))
    )
    (net (code "69") (name "unconnected-(CON1A-GPIO80{slash}EM1D4{slash}EQEP2S-PadA9)") (class "Default")
      (node (ref "CON1") (pin "A9") (pinfunction "GPIO80/EM1D4/EQEP2S_A9") (pintype "passive"))
    )
    (net (code "70") (name "unconnected-(CON1A-GPIO81{slash}EM1D3{slash}EQEP2I-PadA7)") (class "Default")
      (node (ref "CON1") (pin "A7") (pinfunction "GPIO81/EM1D3/EQEP2I_A7") (pintype "passive"))
    )
    (net (code "71") (name "unconnected-(CON1A-GPIO82{slash}EM1D2-PadA5)") (class "Default")
      (node (ref "CON1") (pin "A5") (pinfunction "GPIO82/EM1D2_A5") (pintype "passive"))
    )
    (net (code "72") (name "unconnected-(CON1A-GPIO83{slash}EM1D1-PadA3)") (class "Default")
      (node (ref "CON1") (pin "A3") (pinfunction "GPIO83/EM1D1_A3") (pintype "passive"))
    )
    (net (code "73") (name "unconnected-(CON1A-GPIO85{slash}EM1D0{slash}SCIRXDA{slash}MDRB{slash}MDRA-PadA1)") (class "Default")
      (node (ref "CON1") (pin "A1") (pinfunction "GPIO85/EM1D0/SCIRXDA/MDRB/MDRA_A1") (pintype "passive"))
    )
    (net (code "74") (name "unconnected-(CON1A-GPIO142{slash}SCITXDD-PadA58)") (class "Default")
      (node (ref "CON1") (pin "A58") (pinfunction "GPIO142/SCITXDD_A58") (pintype "passive"))
    )
    (net (code "75") (name "unconnected-(CON1A-GPIO143-PadA56)") (class "Default")
      (node (ref "CON1") (pin "A56") (pinfunction "GPIO143_A56") (pintype "passive"))
    )
    (net (code "76") (name "unconnected-(CON1A-GPIO144-PadA54)") (class "Default")
      (node (ref "CON1") (pin "A54") (pinfunction "GPIO144_A54") (pintype "passive"))
    )
    (net (code "77") (name "unconnected-(CON1A-GPIO145{slash}EPWM1A-PadA50)") (class "Default")
      (node (ref "CON1") (pin "A50") (pinfunction "GPIO145/EPWM1A_A50") (pintype "passive"))
    )
    (net (code "78") (name "unconnected-(CON1A-GPIO146{slash}EPWM1B-PadA48)") (class "Default")
      (node (ref "CON1") (pin "A48") (pinfunction "GPIO146/EPWM1B_A48") (pintype "passive"))
    )
    (net (code "79") (name "unconnected-(CON1A-GPIO147{slash}EPWM2A-PadA46)") (class "Default")
      (node (ref "CON1") (pin "A46") (pinfunction "GPIO147/EPWM2A_A46") (pintype "passive"))
    )
    (net (code "80") (name "unconnected-(CON1A-GPIO148{slash}EPWM2B-PadA44)") (class "Default")
      (node (ref "CON1") (pin "A44") (pinfunction "GPIO148/EPWM2B_A44") (pintype "passive"))
    )
    (net (code "81") (name "unconnected-(CON1A-GPIO149{slash}EPWM3A-PadA42)") (class "Default")
      (node (ref "CON1") (pin "A42") (pinfunction "GPIO149/EPWM3A_A42") (pintype "passive"))
    )
    (net (code "82") (name "unconnected-(CON1A-GPIO150{slash}EPWM3B-PadA40)") (class "Default")
      (node (ref "CON1") (pin "A40") (pinfunction "GPIO150/EPWM3B_A40") (pintype "passive"))
    )
    (net (code "83") (name "unconnected-(CON1A-GPIO151{slash}EPWM4A-PadA38)") (class "Default")
      (node (ref "CON1") (pin "A38") (pinfunction "GPIO151/EPWM4A_A38") (pintype "passive"))
    )
    (net (code "84") (name "unconnected-(CON1A-GPIO152{slash}EPWM4B-PadA36)") (class "Default")
      (node (ref "CON1") (pin "A36") (pinfunction "GPIO152/EPWM4B_A36") (pintype "passive"))
    )
    (net (code "85") (name "unconnected-(CON1A-GPIO154{slash}EPWM5B-PadA32)") (class "Default")
      (node (ref "CON1") (pin "A32") (pinfunction "GPIO154/EPWM5B_A32") (pintype "passive"))
    )
    (net (code "86") (name "unconnected-(CON1A-GPIO156{slash}EPWM6B-PadA28)") (class "Default")
      (node (ref "CON1") (pin "A28") (pinfunction "GPIO156/EPWM6B_A28") (pintype "passive"))
    )
    (net (code "87") (name "unconnected-(CON1A-GPIO158{slash}EPWM7B-PadA24)") (class "Default")
      (node (ref "CON1") (pin "A24") (pinfunction "GPIO158/EPWM7B_A24") (pintype "passive"))
    )
    (net (code "88") (name "unconnected-(CON1A-GPIO160{slash}EPWM8B-PadA20)") (class "Default")
      (node (ref "CON1") (pin "A20") (pinfunction "GPIO160/EPWM8B_A20") (pintype "passive"))
    )
    (net (code "89") (name "unconnected-(CON1A-GPIO162{slash}EPWM9B-PadA16)") (class "Default")
      (node (ref "CON1") (pin "A16") (pinfunction "GPIO162/EPWM9B_A16") (pintype "passive"))
    )
    (net (code "90") (name "unconnected-(CON1A-GPIO164{slash}EPWM10B-PadA12)") (class "Default")
      (node (ref "CON1") (pin "A12") (pinfunction "GPIO164/EPWM10B_A12") (pintype "passive"))
    )
    (net (code "91") (name "unconnected-(CON1A-GPIO166{slash}EPWM11B-PadA8)") (class "Default")
      (node (ref "CON1") (pin "A8") (pinfunction "GPIO166/EPWM11B_A8") (pintype "passive"))
    )
    (net (code "92") (name "unconnected-(CON1A-GPIO168{slash}EPWM12B-PadA4)") (class "Default")
      (node (ref "CON1") (pin "A4") (pinfunction "GPIO168/EPWM12B_A4") (pintype "passive"))
    )
    (net (code "93") (name "unconnected-(CON1A-MCLKRB{slash}EM1D24{slash}EM2D8{slash}OUTPUTXBAR3{slash}SPISIMOB{slash}SD2_D3{slash}SPICLKA{slash}GPIO60-PadA49)") (class "Default")
      (node (ref "CON1") (pin "A49") (pinfunction "MCLKRB/EM1D24/EM2D8/OUTPUTXBAR3/SPISIMOB/SD2_D3/SPICLKA/GPIO60_A49") (pintype "passive"))
    )
    (net (code "94") (name "unconnected-(CON1A-MFSRA{slash}EM1D25{slash}EM2D9{slash}OUTPUTXBAR2{slash}~{SPISTEB}{slash}SD2_C2{slash}SPISOMIA{slash}GPIO59-PadA51)") (class "Default")
      (node (ref "CON1") (pin "A51") (pinfunction "MFSRA/EM1D25/EM2D9/OUTPUTXBAR2/~{SPISTEB}/SD2_C2/SPISOMIA/GPIO59_A51") (pintype "passive"))
    )
    (net (code "95") (name "unconnected-(CON1A-MFSRB{slash}EM1D23{slash}EM2D7{slash}OUTPUTXBAR4{slash}SPISOMIB{slash}SD2_C3{slash}~{SPISTEA}{slash}GPIO61-PadA47)") (class "Default")
      (node (ref "CON1") (pin "A47") (pinfunction "MFSRB/EM1D23/EM2D7/OUTPUTXBAR4/SPISOMIB/SD2_C3/~{SPISTEA}/GPIO61_A47") (pintype "passive"))
    )
    (net (code "96") (name "unconnected-(CON1A-SCIRXDC{slash}EM1D22{slash}EM2D6{slash}EQEP3A{slash}CANRXA{slash}SD2_D4{slash}GPIO62-PadA45)") (class "Default")
      (node (ref "CON1") (pin "A45") (pinfunction "SCIRXDC/EM1D22/EM2D6/EQEP3A/CANRXA/SD2_D4/GPIO62_A45") (pintype "passive"))
    )
    (net (code "97") (name "unconnected-(CON1A-SCITXDC{slash}EM1D21{slash}EM2D5{slash}EQEP3B{slash}CANTXA{slash}SD2_C4{slash}SPISIMOB{slash}GPIO63-PadA43)") (class "Default")
      (node (ref "CON1") (pin "A43") (pinfunction "SCITXDC/EM1D21/EM2D5/EQEP3B/CANTXA/SD2_C4/SPISIMOB/GPIO63_A43") (pintype "passive"))
    )
    (net (code "98") (name "unconnected-(CON1B-EM2A0{slash}EQEP1S{slash}GPIO98-PadB6)") (class "Default")
      (node (ref "CON1") (pin "B6") (pinfunction "EM2A0/EQEP1S/GPIO98_B6") (pintype "passive"))
    )
    (net (code "99") (name "unconnected-(CON1B-EM2A1{slash}EQEP1I{slash}GPIO99-PadB8)") (class "Default")
      (node (ref "CON1") (pin "B8") (pinfunction "EM2A1/EQEP1I/GPIO99_B8") (pintype "passive"))
    )
    (net (code "100") (name "unconnected-(CON1B-EM2A2{slash}EQEP2A{slash}SPISIMOC{slash}GPIO100-PadB14)") (class "Default")
      (node (ref "CON1") (pin "B14") (pinfunction "EM2A2/EQEP2A/SPISIMOC/GPIO100_B14") (pintype "passive"))
    )
    (net (code "101") (name "unconnected-(CON1B-EM2A3{slash}EQEP2B{slash}SPISOMIC{slash}GPIO101-PadB12)") (class "Default")
      (node (ref "CON1") (pin "B12") (pinfunction "EM2A3/EQEP2B/SPISOMIC/GPIO101_B12") (pintype "passive"))
    )
    (net (code "102") (name "unconnected-(CON1B-EM2A4{slash}EQEP2S{slash}SPICLKC{slash}GPIO102-PadB10)") (class "Default")
      (node (ref "CON1") (pin "B10") (pinfunction "EM2A4/EQEP2S/SPICLKC/GPIO102_B10") (pintype "passive"))
    )
    (net (code "103") (name "unconnected-(CON1B-EM2A5{slash}EQEP2I{slash}~{SPISTEC}{slash}GPIO103-PadB16)") (class "Default")
      (node (ref "CON1") (pin "B16") (pinfunction "EM2A5/EQEP2I/~{SPISTEC}/GPIO103_B16") (pintype "passive"))
    )
    (net (code "104") (name "unconnected-(CON1B-EM2DQM0{slash}EQEP1B{slash}GPIO97-PadB4)") (class "Default")
      (node (ref "CON1") (pin "B4") (pinfunction "EM2DQM0/EQEP1B/GPIO97_B4") (pintype "passive"))
    )
    (net (code "105") (name "unconnected-(CON1B-EM2DQM1{slash}EQEP1A{slash}GPIO96-PadB2)") (class "Default")
      (node (ref "CON1") (pin "B2") (pinfunction "EM2DQM1/EQEP1A/GPIO96_B2") (pintype "passive"))
    )
    (net (code "106") (name "unconnected-(CON1B-EPWM1B{slash}MFSRB{slash}SCLA{slash}GPIO1-PadB36)") (class "Default")
      (node (ref "CON1") (pin "B36") (pinfunction "EPWM1B/MFSRB/SCLA/GPIO1_B36") (pintype "passive"))
    )
    (net (code "107") (name "unconnected-(CON1B-EPWM2B{slash}OUTPUTXBAR2{slash}SCLB{slash}MCLKRB{slash}GPIO3-PadB28)") (class "Default")
      (node (ref "CON1") (pin "B28") (pinfunction "EPWM2B/OUTPUTXBAR2/SCLB/MCLKRB/GPIO3_B28") (pintype "passive"))
    )
    (net (code "108") (name "unconnected-(CON1B-EPWM6A{slash}CANRXB{slash}ADCSOCBO{slash}EQEP1A{slash}SCITXDB{slash}UPP-WAIT{slash}GPIO10-PadB59)") (class "Default")
      (node (ref "CON1") (pin "B59") (pinfunction "EPWM6A/CANRXB/ADCSOCBO/EQEP1A/SCITXDB/UPP-WAIT/GPIO10_B59") (pintype "passive"))
    )
    (net (code "109") (name "unconnected-(CON1B-EPWM6B{slash}SCIRXDB{slash}OUTPUTXBAR7{slash}EQEP1B{slash}UPP-STRT{slash}GPIO11-PadB57)") (class "Default")
      (node (ref "CON1") (pin "B57") (pinfunction "EPWM6B/SCIRXDB/OUTPUTXBAR7/EQEP1B/UPP-STRT/GPIO11_B57") (pintype "passive"))
    )
    (net (code "110") (name "unconnected-(CON1B-EPWM7A{slash}CANTXB{slash}MDXB{slash}EQEP1S{slash}SCITXDC{slash}UPP-ENA{slash}GPIO12-PadB55)") (class "Default")
      (node (ref "CON1") (pin "B55") (pinfunction "EPWM7A/CANTXB/MDXB/EQEP1S/SCITXDC/UPP-ENA/GPIO12_B55") (pintype "passive"))
    )
    (net (code "111") (name "unconnected-(CON1B-EPWM7B{slash}CANRXB{slash}MDRB{slash}EQEP1I{slash}SCIRXDC{slash}UPP-D7{slash}GPIO13-PadB58)") (class "Default")
      (node (ref "CON1") (pin "B58") (pinfunction "EPWM7B/CANRXB/MDRB/EQEP1I/SCIRXDC/UPP-D7/GPIO13_B58") (pintype "passive"))
    )
    (net (code "112") (name "unconnected-(CON1B-EPWM8A{slash}SCITXDB{slash}MCLKXB{slash}OUTPUTXBAR3{slash}UPP-D6{slash}GPIO14-PadB56)") (class "Default")
      (node (ref "CON1") (pin "B56") (pinfunction "EPWM8A/SCITXDB/MCLKXB/OUTPUTXBAR3/UPP-D6/GPIO14_B56") (pintype "passive"))
    )
    (net (code "113") (name "unconnected-(CON1B-EPWM8B{slash}SCIRXDB{slash}MFSXB{slash}OUTPUTXBAR4{slash}UPP-D5{slash}GPIO15-PadB54)") (class "Default")
      (node (ref "CON1") (pin "B54") (pinfunction "EPWM8B/SCIRXDB/MFSXB/OUTPUTXBAR4/UPP-D5/GPIO15_B54") (pintype "passive"))
    )
    (net (code "114") (name "unconnected-(CON1B-EPWM9A{slash}SPISIMOA{slash}CANTXB{slash}OUTPUTXBAR7{slash}SD1_D1{slash}UPP-D4{slash}GPIO16-PadB52)") (class "Default")
      (node (ref "CON1") (pin "B52") (pinfunction "EPWM9A/SPISIMOA/CANTXB/OUTPUTXBAR7/SD1_D1/UPP-D4/GPIO16_B52") (pintype "passive"))
    )
    (net (code "115") (name "unconnected-(CON1B-EPWM9B{slash}SPISOMIA{slash}CANRXB{slash}OUTPUTXBAR8{slash}SD1_C1{slash}UPP-D3{slash}GPIO17-PadB50)") (class "Default")
      (node (ref "CON1") (pin "B50") (pinfunction "EPWM9B/SPISOMIA/CANRXB/OUTPUTXBAR8/SD1_C1/UPP-D3/GPIO17_B50") (pintype "passive"))
    )
    (net (code "116") (name "unconnected-(CON1B-EPWM10A{slash}SPICLKA{slash}SCITXDB{slash}CANRXA{slash}SD1_D2{slash}UPP-D2{slash}GPIO18-PadB48)") (class "Default")
      (node (ref "CON1") (pin "B48") (pinfunction "EPWM10A/SPICLKA/SCITXDB/CANRXA/SD1_D2/UPP-D2/GPIO18_B48") (pintype "passive"))
    )
    (net (code "117") (name "unconnected-(CON1B-EPWM10B{slash}~{SPISTEA}{slash}SCIRXDB{slash}CANTXA{slash}SD1_C2{slash}UPP-D1{slash}GPIO19-PadB46)") (class "Default")
      (node (ref "CON1") (pin "B46") (pinfunction "EPWM10B/~{SPISTEA}/SCIRXDB/CANTXA/SD1_C2/UPP-D1/GPIO19_B46") (pintype "passive"))
    )
    (net (code "118") (name "unconnected-(CON1B-EPWM11A{slash}EQEP1A{slash}MDXA{slash}CANTXB{slash}SD1_D3{slash}UPP-D0{slash}GPIO20-PadB44)") (class "Default")
      (node (ref "CON1") (pin "B44") (pinfunction "EPWM11A/EQEP1A/MDXA/CANTXB/SD1_D3/UPP-D0/GPIO20_B44") (pintype "passive"))
    )
    (net (code "119") (name "unconnected-(CON1B-EPWM11B{slash}EQEP1B{slash}MDRA{slash}CANRXB{slash}SD1_C3{slash}UPP-CLK{slash}GPIO21-PadB42)") (class "Default")
      (node (ref "CON1") (pin "B42") (pinfunction "EPWM11B/EQEP1B/MDRA/CANRXB/SD1_C3/UPP-CLK/GPIO21_B42") (pintype "passive"))
    )
    (net (code "120") (name "unconnected-(CON1B-EPWM12A{slash}EQEP1S{slash}MCLKXA{slash}SCITXDB{slash}SPICLKB{slash}SD1_D4{slash}GPIO22-PadB43)") (class "Default")
      (node (ref "CON1") (pin "B43") (pinfunction "EPWM12A/EQEP1S/MCLKXA/SCITXDB/SPICLKB/SD1_D4/GPIO22_B43") (pintype "passive"))
    )
    (net (code "121") (name "unconnected-(CON1B-EQEP1A{slash}EM1A10{slash}SPISIMOC{slash}SD1_D2{slash}GPIO50-PadB21)") (class "Default")
      (node (ref "CON1") (pin "B21") (pinfunction "EQEP1A/EM1A10/SPISIMOC/SD1_D2/GPIO50_B21") (pintype "passive"))
    )
    (net (code "122") (name "unconnected-(CON1B-EQEP1B{slash}EM1A11{slash}SPISOMIC{slash}SD1_C2{slash}GPIO51-PadB23)") (class "Default")
      (node (ref "CON1") (pin "B23") (pinfunction "EQEP1B/EM1A11/SPISOMIC/SD1_C2/GPIO51_B23") (pintype "passive"))
    )
    (net (code "123") (name "unconnected-(CON1B-EQEP1S{slash}EM1A12{slash}SPICLKC{slash}SD1_D3{slash}GPIO52-PadB25)") (class "Default")
      (node (ref "CON1") (pin "B25") (pinfunction "EQEP1S/EM1A12/SPICLKC/SD1_D3/GPIO52_B25") (pintype "passive"))
    )
    (net (code "124") (name "unconnected-(CON1B-GPIO25{slash}OUTPUTXBAR2{slash}EQEP2B{slash}MDRB{slash}SPISOMIB{slash}SD2_C1-PadB30)") (class "Default")
      (node (ref "CON1") (pin "B30") (pinfunction "GPIO25/OUTPUTXBAR2/EQEP2B/MDRB/SPISOMIB/SD2_C1_B30") (pintype "passive"))
    )
    (net (code "125") (name "unconnected-(CON1B-GPIO26{slash}OUTPUTXBAR3{slash}EQEP2I{slash}MCLKXB{slash}SPICLKB{slash}SD2_D2-PadB32)") (class "Default")
      (node (ref "CON1") (pin "B32") (pinfunction "GPIO26/OUTPUTXBAR3/EQEP2I/MCLKXB/SPICLKB/SD2_D2_B32") (pintype "passive"))
    )
    (net (code "126") (name "unconnected-(CON1B-GPIO27{slash}OUTPUTXBAR4{slash}EQEP2S{slash}MFSXB{slash}~{SPISTEB}{slash}SD2_C2-PadB38)") (class "Default")
      (node (ref "CON1") (pin "B38") (pinfunction "GPIO27/OUTPUTXBAR4/EQEP2S/MFSXB/~{SPISTEB}/SD2_C2_B38") (pintype "passive"))
    )
    (net (code "127") (name "unconnected-(CON1B-GPIO38{slash}EM1A0{slash}SCITXDC{slash}CANTXB-PadB1)") (class "Default")
      (node (ref "CON1") (pin "B1") (pinfunction "GPIO38/EM1A0/SCITXDC/CANTXB_B1") (pintype "passive"))
    )
    (net (code "128") (name "unconnected-(CON1B-GPIO39{slash}EM1A1{slash}SCIRXDC{slash}CANRXB-PadB3)") (class "Default")
      (node (ref "CON1") (pin "B3") (pinfunction "GPIO39/EM1A1/SCIRXDC/CANRXB_B3") (pintype "passive"))
    )
    (net (code "129") (name "unconnected-(CON1B-GPIO40{slash}EM1A2{slash}SDAB-PadB5)") (class "Default")
      (node (ref "CON1") (pin "B5") (pinfunction "GPIO40/EM1A2/SDAB_B5") (pintype "passive"))
    )
    (net (code "130") (name "unconnected-(CON1B-GPIO41{slash}EM1A3{slash}SCLB-PadB7)") (class "Default")
      (node (ref "CON1") (pin "B7") (pinfunction "GPIO41/EM1A3/SCLB_B7") (pintype "passive"))
    )
    (net (code "131") (name "unconnected-(CON1B-GPIO44{slash}EM1A4-PadB9)") (class "Default")
      (node (ref "CON1") (pin "B9") (pinfunction "GPIO44/EM1A4_B9") (pintype "passive"))
    )
    (net (code "132") (name "unconnected-(CON1B-GPIO45{slash}EM1A5-PadB11)") (class "Default")
      (node (ref "CON1") (pin "B11") (pinfunction "GPIO45/EM1A5_B11") (pintype "passive"))
    )
    (net (code "133") (name "unconnected-(CON1B-GPIO46{slash}EM1A6{slash}SCIRXDD-PadB13)") (class "Default")
      (node (ref "CON1") (pin "B13") (pinfunction "GPIO46/EM1A6/SCIRXDD_B13") (pintype "passive"))
    )
    (net (code "134") (name "unconnected-(CON1B-GPIO47{slash}EM1A7{slash}SCITXDD-PadB15)") (class "Default")
      (node (ref "CON1") (pin "B15") (pinfunction "GPIO47/EM1A7/SCITXDD_B15") (pintype "passive"))
    )
    (net (code "135") (name "unconnected-(CON1B-GPIO86{slash}EM1A13{slash}EM1CAS{slash}SCITXDB{slash}MCLKXB{slash}MCLKXA-PadB27)") (class "Default")
      (node (ref "CON1") (pin "B27") (pinfunction "GPIO86/EM1A13/EM1CAS/SCITXDB/MCLKXB/MCLKXA_B27") (pintype "passive"))
    )
    (net (code "136") (name "unconnected-(CON1B-GPIO87{slash}EM1A14{slash}EM1RAS{slash}SCIRXDB{slash}MFSXB{slash}MFSXA-PadB29)") (class "Default")
      (node (ref "CON1") (pin "B29") (pinfunction "GPIO87/EM1A14/EM1RAS/SCIRXDB/MFSXB/MFSXA_B29") (pintype "passive"))
    )
    (net (code "137") (name "unconnected-(CON1B-GPIO88{slash}EM1A15{slash}EM1DQM0-PadB31)") (class "Default")
      (node (ref "CON1") (pin "B31") (pinfunction "GPIO88/EM1A15/EM1DQM0_B31") (pintype "passive"))
    )
    (net (code "138") (name "unconnected-(CON1B-GPIO89{slash}EM1A16{slash}EM1DQM1{slash}SCITXDC-PadB33)") (class "Default")
      (node (ref "CON1") (pin "B33") (pinfunction "GPIO89/EM1A16/EM1DQM1/SCITXDC_B33") (pintype "passive"))
    )
    (net (code "139") (name "unconnected-(CON1B-GPIO90{slash}EM1A17{slash}EM1DQM2{slash}SCIRXDC-PadB35)") (class "Default")
      (node (ref "CON1") (pin "B35") (pinfunction "GPIO90/EM1A17/EM1DQM2/SCIRXDC_B35") (pintype "passive"))
    )
    (net (code "140") (name "unconnected-(CON1B-GPIO91{slash}EMIA18{slash}EM1DQM3{slash}SDAA-PadB37)") (class "Default")
      (node (ref "CON1") (pin "B37") (pinfunction "GPIO91/EMIA18/EM1DQM3/SDAA_B37") (pintype "passive"))
    )
    (net (code "141") (name "unconnected-(CON1B-GPIO92{slash}EM1A19{slash}EM1BA1{slash}SCLA-PadB39)") (class "Default")
      (node (ref "CON1") (pin "B39") (pinfunction "GPIO92/EM1A19/EM1BA1/SCLA_B39") (pintype "passive"))
    )
    (net (code "142") (name "unconnected-(CON1B-GPIO93{slash}EM1BA0{slash}SCITXDD-PadB47)") (class "Default")
      (node (ref "CON1") (pin "B47") (pinfunction "GPIO93/EM1BA0/SCITXDD_B47") (pintype "passive"))
    )
    (net (code "143") (name "unconnected-(CON1B-GPIO95-PadB51)") (class "Default")
      (node (ref "CON1") (pin "B51") (pinfunction "GPIO95_B51") (pintype "passive"))
    )
    (net (code "144") (name "unconnected-(CON1B-OUTPUTXBAR1{slash}EQEP2A{slash}MDXB{slash}SPISIMOB{slash}SD2_D1{slash}GPIO24-PadB34)") (class "Default")
      (node (ref "CON1") (pin "B34") (pinfunction "OUTPUTXBAR1/EQEP2A/MDXB/SPISIMOB/SD2_D1/GPIO24_B34") (pintype "passive"))
    )
    (net (code "145") (name "unconnected-(CON1B-OUTPUTXBAR3{slash}EM1A8{slash}SCITXDA{slash}SD1_D1{slash}GPIO48-PadB17)") (class "Default")
      (node (ref "CON1") (pin "B17") (pinfunction "OUTPUTXBAR3/EM1A8/SCITXDA/SD1_D1/GPIO48_B17") (pintype "passive"))
    )
    (net (code "146") (name "unconnected-(CON1B-OUTPUTXBAR4{slash}EM1A9{slash}SCIRXDA{slash}SD1_C1{slash}GPIO49-PadB19)") (class "Default")
      (node (ref "CON1") (pin "B19") (pinfunction "OUTPUTXBAR4/EM1A9/SCIRXDA/SD1_C1/GPIO49_B19") (pintype "passive"))
    )
    (net (code "147") (name "unconnected-(CON1C-ADCIN14{slash}CMPIN4P-PadC33)") (class "Default")
      (node (ref "CON1") (pin "C33") (pinfunction "ADCIN14/CMPIN4P_C33") (pintype "passive"))
    )
    (net (code "148") (name "unconnected-(CON1C-ADCIN15{slash}CMPIN4N-PadC31)") (class "Default")
      (node (ref "CON1") (pin "C31") (pinfunction "ADCIN15/CMPIN4N_C31") (pintype "passive"))
    )
    (net (code "149") (name "unconnected-(CON1C-ADCINA0{slash}DACOUTA-PadC45)") (class "Default")
      (node (ref "CON1") (pin "C45") (pinfunction "ADCINA0/DACOUTA_C45") (pintype "passive"))
    )
    (net (code "150") (name "unconnected-(CON1C-ADCINA1{slash}DACOUTB-PadC47)") (class "Default")
      (node (ref "CON1") (pin "C47") (pinfunction "ADCINA1/DACOUTB_C47") (pintype "passive"))
    )
    (net (code "151") (name "unconnected-(CON1C-ADCINA2{slash}CMPIN1P-PadC41)") (class "Default")
      (node (ref "CON1") (pin "C41") (pinfunction "ADCINA2/CMPIN1P_C41") (pintype "passive"))
    )
    (net (code "152") (name "unconnected-(CON1C-ADCINA3{slash}CMPIN1N-PadC43)") (class "Default")
      (node (ref "CON1") (pin "C43") (pinfunction "ADCINA3/CMPIN1N_C43") (pintype "passive"))
    )
    (net (code "153") (name "unconnected-(CON1C-ADCINA4{slash}CMPIN2P-PadC37)") (class "Default")
      (node (ref "CON1") (pin "C37") (pinfunction "ADCINA4/CMPIN2P_C37") (pintype "passive"))
    )
    (net (code "154") (name "unconnected-(CON1C-ADCINA5{slash}CMPIN2N-PadC39)") (class "Default")
      (node (ref "CON1") (pin "C39") (pinfunction "ADCINA5/CMPIN2N_C39") (pintype "passive"))
    )
    (net (code "155") (name "unconnected-(CON1C-ADCINB0{slash}VDAC-PadC27)") (class "Default")
      (node (ref "CON1") (pin "C27") (pinfunction "ADCINB0/VDAC_C27") (pintype "passive"))
    )
    (net (code "156") (name "unconnected-(CON1C-ADCINB1{slash}DACOUTC-PadC25)") (class "Default")
      (node (ref "CON1") (pin "C25") (pinfunction "ADCINB1/DACOUTC_C25") (pintype "passive"))
    )
    (net (code "157") (name "unconnected-(CON1C-ADCINB2{slash}CMPIN3P-PadC23)") (class "Default")
      (node (ref "CON1") (pin "C23") (pinfunction "ADCINB2/CMPIN3P_C23") (pintype "passive"))
    )
    (net (code "158") (name "unconnected-(CON1C-ADCINB3{slash}CMPIN3N-PadC21)") (class "Default")
      (node (ref "CON1") (pin "C21") (pinfunction "ADCINB3/CMPIN3N_C21") (pintype "passive"))
    )
    (net (code "159") (name "unconnected-(CON1C-ADCINB4-PadC19)") (class "Default")
      (node (ref "CON1") (pin "C19") (pinfunction "ADCINB4_C19") (pintype "passive"))
    )
    (net (code "160") (name "unconnected-(CON1C-ADCINB5-PadC17)") (class "Default")
      (node (ref "CON1") (pin "C17") (pinfunction "ADCINB5_C17") (pintype "passive"))
    )
    (net (code "161") (name "unconnected-(CON1C-ADCINC2{slash}CMPIN6P-PadC51)") (class "Default")
      (node (ref "CON1") (pin "C51") (pinfunction "ADCINC2/CMPIN6P_C51") (pintype "passive"))
    )
    (net (code "162") (name "unconnected-(CON1C-ADCINC3{slash}CMPIN6N-PadC53)") (class "Default")
      (node (ref "CON1") (pin "C53") (pinfunction "ADCINC3/CMPIN6N_C53") (pintype "passive"))
    )
    (net (code "163") (name "unconnected-(CON1C-ADCINC4{slash}CMPIN5P-PadC55)") (class "Default")
      (node (ref "CON1") (pin "C55") (pinfunction "ADCINC4/CMPIN5P_C55") (pintype "passive"))
    )
    (net (code "164") (name "unconnected-(CON1C-ADCINC5{slash}CMPIN5N-PadC57)") (class "Default")
      (node (ref "CON1") (pin "C57") (pinfunction "ADCINC5/CMPIN5N_C57") (pintype "passive"))
    )
    (net (code "165") (name "unconnected-(CON1C-ADCIND0{slash}CMPIN7P-PadC13)") (class "Default")
      (node (ref "CON1") (pin "C13") (pinfunction "ADCIND0/CMPIN7P_C13") (pintype "passive"))
    )
    (net (code "166") (name "unconnected-(CON1C-ADCIND1{slash}CMPIN7N-PadC11)") (class "Default")
      (node (ref "CON1") (pin "C11") (pinfunction "ADCIND1/CMPIN7N_C11") (pintype "passive"))
    )
    (net (code "167") (name "unconnected-(CON1C-ADCIND2{slash}CMPIN8P-PadC9)") (class "Default")
      (node (ref "CON1") (pin "C9") (pinfunction "ADCIND2/CMPIN8P_C9") (pintype "passive"))
    )
    (net (code "168") (name "unconnected-(CON1C-ADCIND3{slash}CMPIN8N-PadC7)") (class "Default")
      (node (ref "CON1") (pin "C7") (pinfunction "ADCIND3/CMPIN8N_C7") (pintype "passive"))
    )
    (net (code "169") (name "unconnected-(CON1C-ADCIND4-PadC5)") (class "Default")
      (node (ref "CON1") (pin "C5") (pinfunction "ADCIND4_C5") (pintype "passive"))
    )
    (net (code "170") (name "unconnected-(CON1C-ADCIND5-PadC3)") (class "Default")
      (node (ref "CON1") (pin "C3") (pinfunction "ADCIND5_C3") (pintype "passive"))
    )
    (net (code "171") (name "unconnected-(CON1C-AGND-PadC1)") (class "Default")
      (node (ref "CON1") (pin "C1") (pinfunction "AGND_C1") (pintype "power_in"))
    )
    (net (code "172") (name "unconnected-(CON1C-AGND-PadC15)") (class "Default")
      (node (ref "CON1") (pin "C15") (pinfunction "AGND_C15") (pintype "power_in"))
    )
    (net (code "173") (name "unconnected-(CON1C-AGND-PadC29)") (class "Default")
      (node (ref "CON1") (pin "C29") (pinfunction "AGND_C29") (pintype "power_in"))
    )
    (net (code "174") (name "unconnected-(CON1C-AGND-PadC35)") (class "Default")
      (node (ref "CON1") (pin "C35") (pinfunction "AGND_C35") (pintype "power_in"))
    )
    (net (code "175") (name "unconnected-(CON1C-AGND-PadC49)") (class "Default")
      (node (ref "CON1") (pin "C49") (pinfunction "AGND_C49") (pintype "power_in"))
    )
    (net (code "176") (name "unconnected-(CON1C-AGND-PadC59)") (class "Default")
      (node (ref "CON1") (pin "C59") (pinfunction "AGND_C59") (pintype "power_in"))
    )
    (net (code "177") (name "unconnected-(CON1C-EM2BA0{slash}GPIO111-PadC48)") (class "Default")
      (node (ref "CON1") (pin "C48") (pinfunction "EM2BA0/GPIO111_C48") (pintype "passive"))
    )
    (net (code "178") (name "unconnected-(CON1C-EM2BA1{slash}GPIO112-PadC52)") (class "Default")
      (node (ref "CON1") (pin "C52") (pinfunction "EM2BA1/GPIO112_C52") (pintype "passive"))
    )
    (net (code "179") (name "unconnected-(CON1C-EM2CAS{slash}GPIO113-PadC44)") (class "Default")
      (node (ref "CON1") (pin "C44") (pinfunction "EM2CAS/GPIO113_C44") (pintype "passive"))
    )
    (net (code "180") (name "unconnected-(CON1C-EM2RAS{slash}GPIO114-PadC46)") (class "Default")
      (node (ref "CON1") (pin "C46") (pinfunction "EM2RAS/GPIO114_C46") (pintype "passive"))
    )
    (net (code "181") (name "unconnected-(CON1C-EM2WAIT{slash}GPIO110-PadC54)") (class "Default")
      (node (ref "CON1") (pin "C54") (pinfunction "EM2WAIT/GPIO110_C54") (pintype "passive"))
    )
    (net (code "182") (name "unconnected-(CON1C-EPWM3A{slash}OUTPUTXBAR3{slash}CANTXA{slash}GPIO4-PadC38)") (class "Default")
      (node (ref "CON1") (pin "C38") (pinfunction "EPWM3A/OUTPUTXBAR3/CANTXA/GPIO4_C38") (pintype "passive"))
    )
    (net (code "183") (name "unconnected-(CON1C-EPWM3B{slash}OUTPUTXBAR3{slash}CANRXA{slash}MFSRA{slash}GPIO5-PadC36)") (class "Default")
      (node (ref "CON1") (pin "C36") (pinfunction "EPWM3B/OUTPUTXBAR3/CANRXA/MFSRA/GPIO5_C36") (pintype "passive"))
    )
    (net (code "184") (name "unconnected-(CON1C-EPWM4B{slash}MCLKRA{slash}OUTPUTXBAR5{slash}EQEP3B{slash}CANRXB{slash}GPIO7-PadC30)") (class "Default")
      (node (ref "CON1") (pin "C30") (pinfunction "EPWM4B/MCLKRA/OUTPUTXBAR5/EQEP3B/CANRXB/GPIO7_C30") (pintype "passive"))
    )
    (net (code "185") (name "unconnected-(CON1C-EPWM5A{slash}CANTXB{slash}ADCSOCAO{slash}EQEP3S{slash}SCITXDA{slash}GPIO8-PadC32)") (class "Default")
      (node (ref "CON1") (pin "C32") (pinfunction "EPWM5A/CANTXB/ADCSOCAO/EQEP3S/SCITXDA/GPIO8_C32") (pintype "passive"))
    )
    (net (code "186") (name "unconnected-(CON1C-GPIO28{slash}SCIRXDA{slash}EM1CS4{slash}OUTPUTXBAR5{slash}EQEP3A{slash}SD2_D3-PadC16)") (class "Default")
      (node (ref "CON1") (pin "C16") (pinfunction "GPIO28/SCIRXDA/EM1CS4/OUTPUTXBAR5/EQEP3A/SD2_D3_C16") (pintype "passive"))
    )
    (net (code "187") (name "unconnected-(CON1C-GPIO29{slash}SCITXDA{slash}EM1SDCKE{slash}OUTPUTXBAR6{slash}EQEP3B{slash}SD2_C3-PadC18)") (class "Default")
      (node (ref "CON1") (pin "C18") (pinfunction "GPIO29/SCITXDA/EM1SDCKE/OUTPUTXBAR6/EQEP3B/SD2_C3_C18") (pintype "passive"))
    )
    (net (code "188") (name "unconnected-(CON1C-GPIO84{slash}SCITXDA{slash}MDXB{slash}MDXA-PadC42)") (class "Default")
      (node (ref "CON1") (pin "C42") (pinfunction "GPIO84/SCITXDA/MDXB/MDXA_C42") (pintype "passive"))
    )
    (net (code "189") (name "unconnected-(CON1C-GPIO108{slash}EM2A10-PadC56)") (class "Default")
      (node (ref "CON1") (pin "C56") (pinfunction "GPIO108/EM2A10_C56") (pintype "passive"))
    )
    (net (code "190") (name "unconnected-(CON1C-GPIO109{slash}EM2A11-PadC50)") (class "Default")
      (node (ref "CON1") (pin "C50") (pinfunction "GPIO109/EM2A11_C50") (pintype "passive"))
    )
    (net (code "191") (name "unconnected-(CON1C-GPIO122{slash}SPISIMOC{slash}SD1_D1-PadC20)") (class "Default")
      (node (ref "CON1") (pin "C20") (pinfunction "GPIO122/SPISIMOC/SD1_D1_C20") (pintype "passive"))
    )
    (net (code "192") (name "unconnected-(CON1C-GPIO123{slash}SPISOMIC{slash}SD1_C1-PadC22)") (class "Default")
      (node (ref "CON1") (pin "C22") (pinfunction "GPIO123/SPISOMIC/SD1_C1_C22") (pintype "passive"))
    )
    (net (code "193") (name "unconnected-(CON1C-GPIO124{slash}SPICLKC{slash}SD1_D2-PadC24)") (class "Default")
      (node (ref "CON1") (pin "C24") (pinfunction "GPIO124/SPICLKC/SD1_D2_C24") (pintype "passive"))
    )
    (net (code "194") (name "unconnected-(CON1C-GPIO125{slash}~{SPISTEC}{slash}SD1_C2-PadC26)") (class "Default")
      (node (ref "CON1") (pin "C26") (pinfunction "GPIO125/~{SPISTEC}/SD1_C2_C26") (pintype "passive"))
    )
    (net (code "195") (name "unconnected-(CON1C-~{EM2CS0}{slash}GPIO115-PadC58)") (class "Default")
      (node (ref "CON1") (pin "C58") (pinfunction "~{EM2CS0}/GPIO115_C58") (pintype "passive"))
    )
    (net (code "196") (name "unconnected-(CON1D-EM2CLK{slash}GPIO118-PadD49)") (class "Default")
      (node (ref "CON1") (pin "D49") (pinfunction "EM2CLK/GPIO118_D49") (pintype "passive"))
    )
    (net (code "197") (name "unconnected-(CON1D-EM2SDCKE{slash}GPIO117-PadD47)") (class "Default")
      (node (ref "CON1") (pin "D47") (pinfunction "EM2SDCKE/GPIO117_D47") (pintype "passive"))
    )
    (net (code "198") (name "unconnected-(CON1D-EPWM1A{slash}SDAA{slash}GPIO0-PadD14)") (class "Default")
      (node (ref "CON1") (pin "D14") (pinfunction "EPWM1A/SDAA/GPIO0_D14") (pintype "passive"))
    )
    (net (code "199") (name "unconnected-(CON1D-EPWM2A{slash}OUTPUTXBAR1{slash}SDAB{slash}GPIO2-PadD16)") (class "Default")
      (node (ref "CON1") (pin "D16") (pinfunction "EPWM2A/OUTPUTXBAR1/SDAB/GPIO2_D16") (pintype "passive"))
    )
    (net (code "200") (name "unconnected-(CON1D-EPWM4A{slash}OUTPUTXBAR4{slash}EPWMSYNC0{slash}EQEP3A{slash}CANTXB{slash}GPIO6-PadD18)") (class "Default")
      (node (ref "CON1") (pin "D18") (pinfunction "EPWM4A/OUTPUTXBAR4/EPWMSYNC0/EQEP3A/CANTXB/GPIO6_D18") (pintype "passive"))
    )
    (net (code "201") (name "unconnected-(CON1D-EPWM5B{slash}OUTPUTXBAR6{slash}EQEP3I{slash}SCITXDB{slash}SCIRXDA{slash}GPIO9-PadD20)") (class "Default")
      (node (ref "CON1") (pin "D20") (pinfunction "EPWM5B/OUTPUTXBAR6/EQEP3I/SCITXDB/SCIRXDA/GPIO9_D20") (pintype "passive"))
    )
    (net (code "202") (name "unconnected-(CON1D-EQEP1I{slash}EM1D31{slash}EM2D15{slash}~{SPISTEC}{slash}SD1_C3{slash}GPIO53-PadD59)") (class "Default")
      (node (ref "CON1") (pin "D59") (pinfunction "EQEP1I/EM1D31/EM2D15/~{SPISTEC}/SD1_C3/GPIO53_D59") (pintype "passive"))
    )
    (net (code "203") (name "unconnected-(CON1D-GPIO30{slash}CANRXA{slash}EM1CLK{slash}OUTPUTXBAR7{slash}EQEP3S{slash}SD2_D4-PadD46)") (class "Default")
      (node (ref "CON1") (pin "D46") (pinfunction "GPIO30/CANRXA/EM1CLK/OUTPUTXBAR7/EQEP3S/SD2_D4_D46") (pintype "passive"))
    )
    (net (code "204") (name "unconnected-(CON1D-GPIO31{slash}CANTXA{slash}~{EM1WE}{slash}OUTPUTXBAR8{slash}EQEP3I{slash}SD2_C4-PadD48)") (class "Default")
      (node (ref "CON1") (pin "D48") (pinfunction "GPIO31/CANTXA/~{EM1WE}/OUTPUTXBAR8/EQEP3I/SD2_C4_D48") (pintype "passive"))
    )
    (net (code "205") (name "unconnected-(CON1D-GPIO32{slash}SDAA{slash}~{EM1CS0}-PadD33)") (class "Default")
      (node (ref "CON1") (pin "D33") (pinfunction "GPIO32/SDAA/~{EM1CS0}_D33") (pintype "passive"))
    )
    (net (code "206") (name "unconnected-(CON1D-GPIO33{slash}SCLA{slash}EM1RNW-PadD31)") (class "Default")
      (node (ref "CON1") (pin "D31") (pinfunction "GPIO33/SCLA/EM1RNW_D31") (pintype "passive"))
    )
    (net (code "207") (name "unconnected-(CON1D-GPIO34{slash}OUTPUTXBAR1{slash}~{EM1CS2}{slash}SDAB-PadD50)") (class "Default")
      (node (ref "CON1") (pin "D50") (pinfunction "GPIO34/OUTPUTXBAR1/~{EM1CS2}/SDAB_D50") (pintype "passive"))
    )
    (net (code "208") (name "unconnected-(CON1D-GPIO35{slash}SCIRXDA{slash}~{EM1CS3}{slash}SCLB-PadD52)") (class "Default")
      (node (ref "CON1") (pin "D52") (pinfunction "GPIO35/SCIRXDA/~{EM1CS3}/SCLB_D52") (pintype "passive"))
    )
    (net (code "209") (name "unconnected-(CON1D-GPIO36{slash}SCITXDA{slash}EM1WAIT{slash}CANRXA-PadD54)") (class "Default")
      (node (ref "CON1") (pin "D54") (pinfunction "GPIO36/SCITXDA/EM1WAIT/CANRXA_D54") (pintype "passive"))
    )
    (net (code "210") (name "unconnected-(CON1D-GPIO37{slash}OUTPUTXBAR2{slash}~{EM1OE}{slash}CANTXA-PadD56)") (class "Default")
      (node (ref "CON1") (pin "D56") (pinfunction "GPIO37/OUTPUTXBAR2/~{EM1OE}/CANTXA_D56") (pintype "passive"))
    )
    (net (code "211") (name "unconnected-(CON1D-GPIO42{slash}SDAA{slash}SCITXDA{slash}USB0DM-PadD10)") (class "Default")
      (node (ref "CON1") (pin "D10") (pinfunction "GPIO42/SDAA/SCITXDA/USB0DM_D10") (pintype "passive"))
    )
    (net (code "212") (name "unconnected-(CON1D-GPIO43{slash}SCLA{slash}SCIRXDA{slash}USB0DP-PadD8)") (class "Default")
      (node (ref "CON1") (pin "D8") (pinfunction "GPIO43/SCLA/SCIRXDA/USB0DP_D8") (pintype "passive"))
    )
    (net (code "213") (name "unconnected-(CON1D-GPIO119{slash}EM2RNW-PadD51)") (class "Default")
      (node (ref "CON1") (pin "D51") (pinfunction "GPIO119/EM2RNW_D51") (pintype "passive"))
    )
    (net (code "214") (name "unconnected-(CON1D-GPIO120{slash}~{EM2WE}{slash}USB0PFLT-PadD4)") (class "Default")
      (node (ref "CON1") (pin "D4") (pinfunction "GPIO120/~{EM2WE}/USB0PFLT_D4") (pintype "passive"))
    )
    (net (code "215") (name "unconnected-(CON1D-GPIO121{slash}USB0EPEN{slash}~{EM2OE}-PadD2)") (class "Default")
      (node (ref "CON1") (pin "D2") (pinfunction "GPIO121/USB0EPEN/~{EM2OE}_D2") (pintype "passive"))
    )
    (net (code "216") (name "unconnected-(CON1D-GPIO126{slash}SD1_D3-PadD43)") (class "Default")
      (node (ref "CON1") (pin "D43") (pinfunction "GPIO126/SD1_D3_D43") (pintype "passive"))
    )
    (net (code "217") (name "unconnected-(CON1D-GPIO127{slash}SD1_C3-PadD39)") (class "Default")
      (node (ref "CON1") (pin "D39") (pinfunction "GPIO127/SD1_C3_D39") (pintype "passive"))
    )
    (net (code "218") (name "unconnected-(CON1D-GPIO128{slash}SD1_D4-PadD41)") (class "Default")
      (node (ref "CON1") (pin "D41") (pinfunction "GPIO128/SD1_D4_D41") (pintype "passive"))
    )
    (net (code "219") (name "unconnected-(CON1D-GPIO129{slash}SD1_C4-PadD45)") (class "Default")
      (node (ref "CON1") (pin "D45") (pinfunction "GPIO129/SD1_C4_D45") (pintype "passive"))
    )
    (net (code "220") (name "unconnected-(CON1D-GPIO130{slash}SD2_D1-PadD1)") (class "Default")
      (node (ref "CON1") (pin "D1") (pinfunction "GPIO130/SD2_D1_D1") (pintype "passive"))
    )
    (net (code "221") (name "unconnected-(CON1D-GPIO131{slash}SD2_C1-PadD3)") (class "Default")
      (node (ref "CON1") (pin "D3") (pinfunction "GPIO131/SD2_C1_D3") (pintype "passive"))
    )
    (net (code "222") (name "unconnected-(CON1D-GPIO132{slash}SD2_D2-PadD5)") (class "Default")
      (node (ref "CON1") (pin "D5") (pinfunction "GPIO132/SD2_D2_D5") (pintype "passive"))
    )
    (net (code "223") (name "unconnected-(CON1D-GPIO133{slash}AUXCLKIN{slash}SD2_C2-PadD7)") (class "Default")
      (node (ref "CON1") (pin "D7") (pinfunction "GPIO133/AUXCLKIN/SD2_C2_D7") (pintype "passive"))
    )
    (net (code "224") (name "unconnected-(CON1D-GPIO134{slash}SD2_D3-PadD9)") (class "Default")
      (node (ref "CON1") (pin "D9") (pinfunction "GPIO134/SD2_D3_D9") (pintype "passive"))
    )
    (net (code "225") (name "unconnected-(CON1D-GPIO137{slash}SD2_C4{slash}SCITXDB-PadD15)") (class "Default")
      (node (ref "CON1") (pin "D15") (pinfunction "GPIO137/SD2_C4/SCITXDB_D15") (pintype "passive"))
    )
    (net (code "226") (name "unconnected-(CON1D-GPIO138{slash}SCIRXDB-PadD53)") (class "Default")
      (node (ref "CON1") (pin "D53") (pinfunction "GPIO138/SCIRXDB_D53") (pintype "passive"))
    )
    (net (code "227") (name "unconnected-(CON1D-GPIO139{slash}SCIRXDC-PadD22)") (class "Default")
      (node (ref "CON1") (pin "D22") (pinfunction "GPIO139/SCIRXDC_D22") (pintype "passive"))
    )
    (net (code "228") (name "unconnected-(CON1D-GPIO140{slash}SCITXDC-PadD24)") (class "Default")
      (node (ref "CON1") (pin "D24") (pinfunction "GPIO140/SCITXDC_D24") (pintype "passive"))
    )
    (net (code "229") (name "unconnected-(CON1D-GPIO141{slash}SCIRXDD-PadD26)") (class "Default")
      (node (ref "CON1") (pin "D26") (pinfunction "GPIO141/SCIRXDD_D26") (pintype "passive"))
    )
    (net (code "230") (name "unconnected-(CON1D-MONITOR_1V2OUT-PadD40)") (class "Default")
      (node (ref "CON1") (pin "D40") (pinfunction "MONITOR_1V2OUT_D40") (pintype "passive"))
    )
    (net (code "231") (name "unconnected-(CON1D-SPISIMOA{slash}EM1D30{slash}EM2D14{slash}EQEP2A{slash}SCITXDB{slash}SD1_D4{slash}GPIO54-PadD57)") (class "Default")
      (node (ref "CON1") (pin "D57") (pinfunction "SPISIMOA/EM1D30/EM2D14/EQEP2A/SCITXDB/SD1_D4/GPIO54_D57") (pintype "passive"))
    )
    (net (code "232") (name "unconnected-(CON1D-SYS_RESET_OUTPUT-PadD32)") (class "Default")
      (node (ref "CON1") (pin "D32") (pinfunction "SYS_RESET_OUTPUT_D32") (pintype "passive"))
    )
    (net (code "233") (name "unconnected-(CON1D-~{EM2CS2}{slash}GPIO116-PadD37)") (class "Default")
      (node (ref "CON1") (pin "D37") (pinfunction "~{EM2CS2}/GPIO116_D37") (pintype "passive"))
    )
    (net (code "234") (name "unconnected-(SD-D1-Pad8)") (class "Default")
      (node (ref "SD") (pin "8") (pinfunction "D1_8") (pintype "passive"))
    )
    (net (code "235") (name "unconnected-(SD-D2-Pad1)") (class "Default")
      (node (ref "SD") (pin "1") (pinfunction "D2_1") (pintype "passive"))
    )
  )
)
